# canbus_module.net
KiCad netlist of a schematic drawn in EAGLE
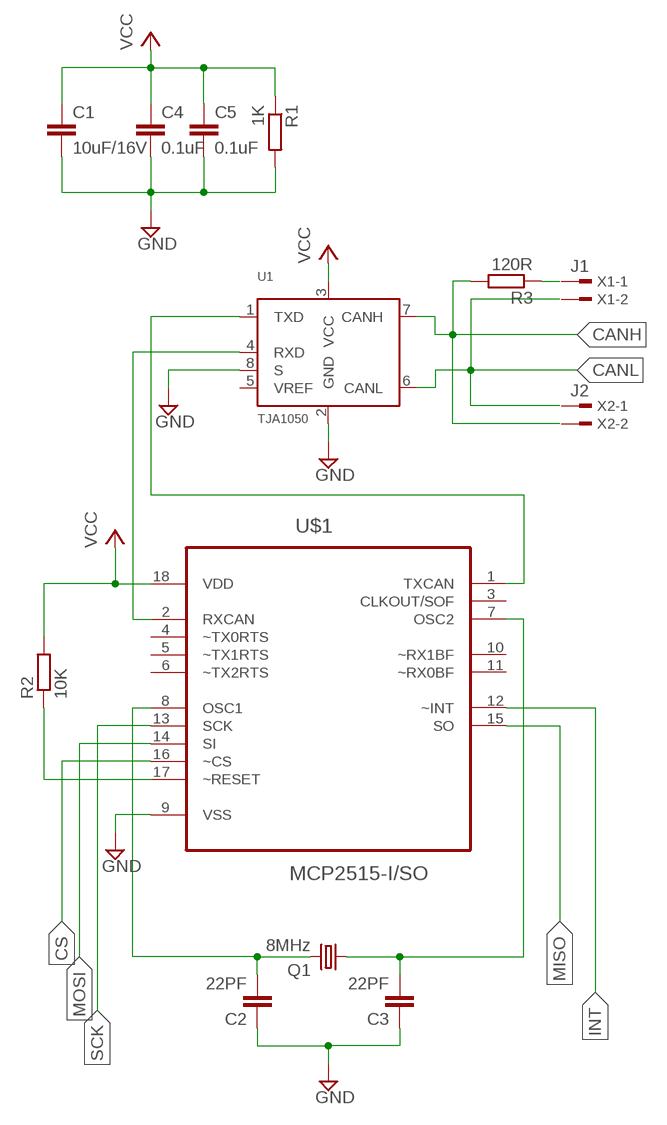
[diagram p0: schematic, sheet 1]

(export (version "E")
  (design (tool "Eeschema 10.0.6"))
  (components
    (comp (ref "C1")
      (value "10uF/16V")
      (footprint "eagle-import:C0805")
      (libsource (lib "eagle-import") (part "C-EUC0805"))
    )
    (comp (ref "C2")
      (value "22PF")
      (footprint "eagle-import:C0805")
      (libsource (lib "eagle-import") (part "C-EUC0805"))
    )
    (comp (ref "C3")
      (value "22PF")
      (footprint "eagle-import:C0805")
      (libsource (lib "eagle-import") (part "C-EUC0805"))
    )
    (comp (ref "C4")
      (value "0.1uF")
      (footprint "eagle-import:C0805")
      (libsource (lib "eagle-import") (part "C-EUC0805"))
    )
    (comp (ref "C5")
      (value "0.1uF")
      (footprint "eagle-import:C0805")
      (libsource (lib "eagle-import") (part "C-EUC0805"))
    )
    (comp (ref "Q1")
      (value "8MHz")
      (footprint "eagle-import:HC49_S")
      (libsource (lib "eagle-import") (part "CRYSTALHC49S"))
    )
    (comp (ref "R1")
      (value "1K")
      (footprint "eagle-import:M0805")
      (libsource (lib "eagle-import") (part "R-EU_M0805"))
    )
    (comp (ref "R2")
      (value "10K")
      (footprint "eagle-import:M0805")
      (libsource (lib "eagle-import") (part "R-EU_M0805"))
    )
    (comp (ref "R3")
      (value "120R")
      (footprint "eagle-import:M0805")
      (libsource (lib "eagle-import") (part "R-EU_M0805"))
    )
    (comp (ref "U$1")
      (value "MCP2515-I/SO")
      (footprint "eagle-import:SOIC127P1034X264-18N")
      (fields (field (name "MF") "Microchip"))
      (libsource (lib "eagle-import") (part "MCP2515-I/SO"))
    )
    (comp (ref "U1")
      (value "TJA1050")
      (footprint "eagle-import:SOT96-1")
      (fields (field (name "MF") "NXP Semiconductors"))
      (libsource (lib "eagle-import") (part "TJA1050"))
    )
    (comp (ref "X1")
      (value "J1")
      (footprint "eagle-import:TSW-102-XX-G-S")
      (fields (field (name "MF") "Samtec Inc.") (field (name "MPN") "TSW-102-07-G-S"))
      (libsource (lib "eagle-import") (part "TSW-102--G-S07"))
    )
    (comp (ref "X2")
      (value "J2")
      (footprint "eagle-import:TSW-102-XX-G-S")
      (fields (field (name "MF") "Samtec Inc.") (field (name "MPN") "TSW-102-07-G-S"))
      (libsource (lib "eagle-import") (part "TSW-102--G-S07"))
    )
  )
  (nets
    (net (code "1") (name "CANH") (class "Default")
      (node (ref "R3") (pin "2") (pinfunction "2_2") (pintype "passive"))
      (node (ref "U1") (pin "7") (pinfunction "CANH_7") (pintype "bidirectional"))
    )
    (net (code "2") (name "CANL") (class "Default")
      (node (ref "U1") (pin "6") (pinfunction "CANL_6") (pintype "bidirectional"))
    )
    (net (code "3") (name "CS") (class "Default")
      (node (ref "U$1") (pin "16") (pinfunction "~{CS}_16") (pintype "input"))
    )
    (net (code "4") (name "GND") (class "Default")
      (node (ref "C1") (pin "2") (pinfunction "2_2") (pintype "passive"))
      (node (ref "C2") (pin "1") (pinfunction "1_1") (pintype "passive"))
      (node (ref "C3") (pin "1") (pinfunction "1_1") (pintype "passive"))
      (node (ref "C4") (pin "2") (pinfunction "2_2") (pintype "passive"))
      (node (ref "C5") (pin "2") (pinfunction "2_2") (pintype "passive"))
      (node (ref "R1") (pin "2") (pinfunction "2_2") (pintype "passive"))
      (node (ref "U$1") (pin "9") (pinfunction "VSS_9") (pintype "power_in"))
      (node (ref "U1") (pin "2") (pinfunction "GND_2") (pintype "bidirectional"))
      (node (ref "U1") (pin "8") (pinfunction "S_8") (pintype "power_in"))
    )
    (net (code "5") (name "INT") (class "Default")
      (node (ref "U$1") (pin "12") (pinfunction "~{INT}_12") (pintype "output"))
    )
    (net (code "6") (name "MISO") (class "Default")
      (node (ref "U$1") (pin "15") (pinfunction "SO_15") (pintype "output"))
    )
    (net (code "7") (name "MOSI") (class "Default")
      (node (ref "U$1") (pin "14") (pinfunction "SI_14") (pintype "input"))
    )
    (net (code "8") (name "Net-(U$1-OSC1)") (class "Default")
      (node (ref "C2") (pin "2") (pinfunction "2_2") (pintype "passive"))
      (node (ref "Q1") (pin "2") (pinfunction "2_2") (pintype "passive"))
      (node (ref "U$1") (pin "8") (pinfunction "OSC1_8") (pintype "input"))
    )
    (net (code "9") (name "Net-(U$1-OSC2)") (class "Default")
      (node (ref "C3") (pin "2") (pinfunction "2_2") (pintype "passive"))
      (node (ref "Q1") (pin "1") (pinfunction "1_1") (pintype "passive"))
      (node (ref "U$1") (pin "7") (pinfunction "OSC2_7") (pintype "output"))
    )
    (net (code "10") (name "Net-(U$1-RXCAN)") (class "Default")
      (node (ref "U$1") (pin "2") (pinfunction "RXCAN_2") (pintype "input"))
      (node (ref "U1") (pin "4") (pinfunction "RXD_4") (pintype "bidirectional"))
    )
    (net (code "11") (name "Net-(U$1-TXCAN)") (class "Default")
      (node (ref "U$1") (pin "1") (pinfunction "TXCAN_1") (pintype "output"))
      (node (ref "U1") (pin "1") (pinfunction "TXD_1") (pintype "output"))
    )
    (net (code "12") (name "Net-(U$1-~{RESET})") (class "Default")
      (node (ref "R2") (pin "1") (pinfunction "1_1") (pintype "passive"))
      (node (ref "U$1") (pin "17") (pinfunction "~{RESET}_17") (pintype "input"))
    )
    (net (code "13") (name "SCK") (class "Default")
      (node (ref "U$1") (pin "13") (pinfunction "SCK_13") (pintype "input"))
    )
    (net (code "14") (name "VCC") (class "Default")
      (node (ref "C1") (pin "1") (pinfunction "1_1") (pintype "passive"))
      (node (ref "C4") (pin "1") (pinfunction "1_1") (pintype "passive"))
      (node (ref "C5") (pin "1") (pinfunction "1_1") (pintype "passive"))
      (node (ref "R1") (pin "1") (pinfunction "1_1") (pintype "passive"))
      (node (ref "R2") (pin "2") (pinfunction "2_2") (pintype "passive"))
      (node (ref "U$1") (pin "18") (pinfunction "VDD_18") (pintype "power_in"))
      (node (ref "U1") (pin "3") (pinfunction "VCC_3") (pintype "bidirectional"))
    )
    (net (code "15") (name "unconnected-(R3-Pad1)") (class "Default")
      (node (ref "R3") (pin "1") (pinfunction "1_1") (pintype "passive"))
    )
    (net (code "16") (name "unconnected-(U$1-CLKOUT{slash}SOF-Pad3)") (class "Default")
      (node (ref "U$1") (pin "3") (pinfunction "CLKOUT/SOF_3") (pintype "output"))
    )
    (net (code "17") (name "unconnected-(U$1-~{RX0BF}-Pad11)") (class "Default")
      (node (ref "U$1") (pin "11") (pinfunction "~{RX0BF}_11") (pintype "output"))
    )
    (net (code "18") (name "unconnected-(U$1-~{RX1BF}-Pad10)") (class "Default")
      (node (ref "U$1") (pin "10") (pinfunction "~{RX1BF}_10") (pintype "output"))
    )
    (net (code "19") (name "unconnected-(U$1-~{TX0RTS}-Pad4)") (class "Default")
      (node (ref "U$1") (pin "4") (pinfunction "~{TX0RTS}_4") (pintype "input"))
    )
    (net (code "20") (name "unconnected-(U$1-~{TX1RTS}-Pad5)") (class "Default")
      (node (ref "U$1") (pin "5") (pinfunction "~{TX1RTS}_5") (pintype "input"))
    )
    (net (code "21") (name "unconnected-(U$1-~{TX2RTS}-Pad6)") (class "Default")
      (node (ref "U$1") (pin "6") (pinfunction "~{TX2RTS}_6") (pintype "input"))
    )
    (net (code "22") (name "unconnected-(U1-VREF-Pad5)") (class "Default")
      (node (ref "U1") (pin "5") (pinfunction "VREF_5") (pintype "passive"))
    )
    (net (code "23") (name "unconnected-(X1-Pad1)") (class "Default")
      (node (ref "X1") (pin "1") (pinfunction "1_1") (pintype "passive"))
    )
    (net (code "24") (name "unconnected-(X1B-1-Pad2)") (class "Default")
      (node (ref "X1") (pin "2") (pinfunction "1_2") (pintype "passive"))
    )
    (net (code "25") (name "unconnected-(X2-Pad1)") (class "Default")
      (node (ref "X2") (pin "1") (pinfunction "1_1") (pintype "passive"))
    )
    (net (code "26") (name "unconnected-(X2B-1-Pad2)") (class "Default")
      (node (ref "X2") (pin "2") (pinfunction "1_2") (pintype "passive"))
    )
  )
)
